# Dual_Power_Supply_Design.net
KiCad netlist of a schematic drawn in EAGLE
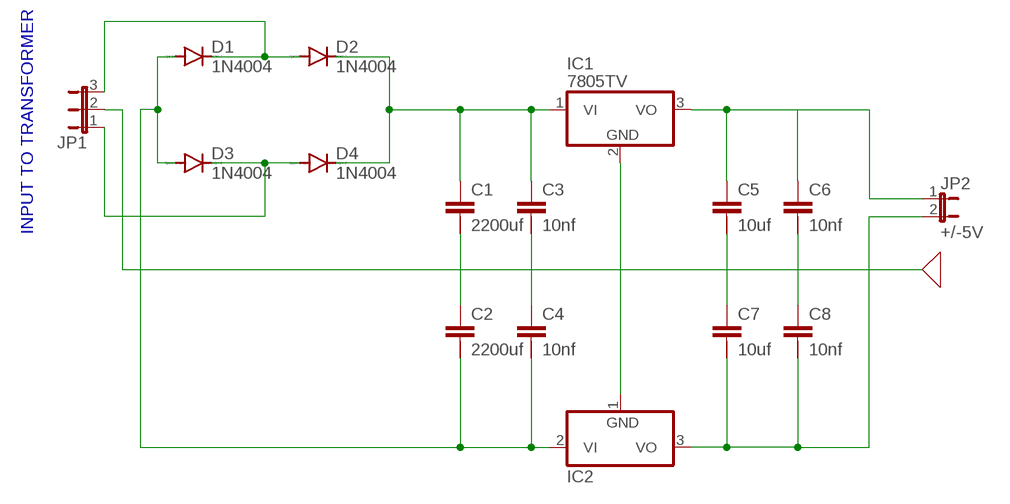
[diagram p0: schematic, sheet 1]

(export (version "E")
  (design (tool "Eeschema 10.0.6"))
  (components
    (comp (ref "C1")
      (value "2200uf")
      (footprint "eagle-import:C2.5_5-2")
      (libsource (lib "eagle-import") (part "C-2.5-5/2"))
    )
    (comp (ref "C2")
      (value "2200uf")
      (footprint "eagle-import:C2.5_5-2")
      (libsource (lib "eagle-import") (part "C-2.5-5/2"))
    )
    (comp (ref "C3")
      (value "10nf")
      (footprint "eagle-import:C2.5_5-2")
      (libsource (lib "eagle-import") (part "C-2.5-5/2"))
    )
    (comp (ref "C4")
      (value "10nf")
      (footprint "eagle-import:C2.5_5-2")
      (libsource (lib "eagle-import") (part "C-2.5-5/2"))
    )
    (comp (ref "C5")
      (value "10uf")
      (footprint "eagle-import:C2.5_5-2")
      (libsource (lib "eagle-import") (part "C-2.5-5/2"))
    )
    (comp (ref "C6")
      (value "10nf")
      (footprint "eagle-import:C2.5_5-2")
      (libsource (lib "eagle-import") (part "C-2.5-5/2"))
    )
    (comp (ref "C7")
      (value "10uf")
      (footprint "eagle-import:C2.5_5-2")
      (libsource (lib "eagle-import") (part "C-2.5-5/2"))
    )
    (comp (ref "C8")
      (value "10nf")
      (footprint "eagle-import:C2.5_5-2")
      (libsource (lib "eagle-import") (part "C-2.5-5/2"))
    )
    (comp (ref "D1")
      (value "1N4004")
      (footprint "eagle-import:DO41-10")
      (libsource (lib "eagle-import") (part "1N4004"))
    )
    (comp (ref "D2")
      (value "1N4004")
      (footprint "eagle-import:DO41-10")
      (libsource (lib "eagle-import") (part "1N4004"))
    )
    (comp (ref "D3")
      (value "1N4004")
      (footprint "eagle-import:DO41-10")
      (libsource (lib "eagle-import") (part "1N4004"))
    )
    (comp (ref "D4")
      (value "1N4004")
      (footprint "eagle-import:DO41-10")
      (libsource (lib "eagle-import") (part "1N4004"))
    )
    (comp (ref "IC1")
      (value "7805TV")
      (footprint "eagle-import:TO220V")
      (libsource (lib "eagle-import") (part "78TV05"))
    )
    (comp (ref "IC2")
      (value "7905T")
      (footprint "eagle-import:TO220H")
      (libsource (lib "eagle-import") (part "79T05"))
    )
    (comp (ref "JP1")
      (value "JP2W")
      (footprint "eagle-import:JP2W")
      (libsource (lib "eagle-import") (part "JP2W"))
    )
    (comp (ref "JP2")
      (value "+/-5V")
      (footprint "eagle-import:JP1")
      (libsource (lib "eagle-import") (part "JP1E"))
    )
  )
  (nets
    (net (code "2") (name "Net-(C1-Pad2)") (class "Default")
      (node (ref "C1") (pin "2") (pinfunction "2_2") (pintype "passive"))
      (node (ref "C2") (pin "1") (pinfunction "1_1") (pintype "passive"))
    )
    (net (code "3") (name "Net-(C3-Pad2)") (class "Default")
      (node (ref "C3") (pin "2") (pinfunction "2_2") (pintype "passive"))
      (node (ref "C4") (pin "1") (pinfunction "1_1") (pintype "passive"))
    )
    (net (code "4") (name "Net-(C5-Pad2)") (class "Default")
      (node (ref "C5") (pin "2") (pinfunction "2_2") (pintype "passive"))
      (node (ref "C7") (pin "1") (pinfunction "1_1") (pintype "passive"))
    )
    (net (code "5") (name "Net-(C6-Pad2)") (class "Default")
      (node (ref "C6") (pin "2") (pinfunction "2_2") (pintype "passive"))
      (node (ref "C8") (pin "1") (pinfunction "1_1") (pintype "passive"))
    )
    (net (code "6") (name "Net-(D1-PadC)") (class "Default")
      (node (ref "D1") (pin "C") (pinfunction "C_C") (pintype "passive"))
      (node (ref "D2") (pin "A") (pinfunction "A_A") (pintype "passive"))
      (node (ref "JP1") (pin "3") (pinfunction "3_3") (pintype "passive"))
    )
    (net (code "7") (name "Net-(D3-PadC)") (class "Default")
      (node (ref "D3") (pin "C") (pinfunction "C_C") (pintype "passive"))
      (node (ref "D4") (pin "A") (pinfunction "A_A") (pintype "passive"))
      (node (ref "JP1") (pin "1") (pinfunction "1_1") (pintype "passive"))
    )
    (net (code "8") (name "Net-(IC1-GND)") (class "Default")
      (node (ref "IC1") (pin "2") (pinfunction "GND_2") (pintype "passive"))
      (node (ref "IC2") (pin "1") (pinfunction "GND_1") (pintype "passive"))
    )
    (net (code "9") (name "Net-(IC1-VI)") (class "Default")
      (node (ref "C1") (pin "1") (pinfunction "1_1") (pintype "passive"))
      (node (ref "C3") (pin "1") (pinfunction "1_1") (pintype "passive"))
      (node (ref "D2") (pin "C") (pinfunction "C_C") (pintype "passive"))
      (node (ref "D4") (pin "C") (pinfunction "C_C") (pintype "passive"))
      (node (ref "IC1") (pin "1") (pinfunction "VI_1") (pintype "input"))
    )
    (net (code "10") (name "Net-(IC1-VO)") (class "Default")
      (node (ref "C5") (pin "1") (pinfunction "1_1") (pintype "passive"))
      (node (ref "IC1") (pin "3") (pinfunction "VO_3") (pintype "passive"))
      (node (ref "JP2") (pin "1") (pinfunction "1_1") (pintype "passive"))
    )
    (net (code "11") (name "Net-(IC2-VI)") (class "Default")
      (node (ref "C2") (pin "2") (pinfunction "2_2") (pintype "passive"))
      (node (ref "C4") (pin "2") (pinfunction "2_2") (pintype "passive"))
      (node (ref "D1") (pin "A") (pinfunction "A_A") (pintype "passive"))
      (node (ref "D3") (pin "A") (pinfunction "A_A") (pintype "passive"))
      (node (ref "IC2") (pin "2") (pinfunction "VI_2") (pintype "input"))
    )
    (net (code "12") (name "Net-(IC2-VO)") (class "Default")
      (node (ref "C7") (pin "2") (pinfunction "2_2") (pintype "passive"))
      (node (ref "C8") (pin "2") (pinfunction "2_2") (pintype "passive"))
      (node (ref "IC2") (pin "3") (pinfunction "VO_3") (pintype "passive"))
      (node (ref "JP2") (pin "2") (pinfunction "2_2") (pintype "passive"))
    )
    (net (code "13") (name "unconnected-(C1-Pad3)") (class "Default")
      (node (ref "C1") (pin "3") (pinfunction "3_3") (pintype "passive"))
    )
    (net (code "14") (name "unconnected-(C2-Pad3)") (class "Default")
      (node (ref "C2") (pin "3") (pinfunction "3_3") (pintype "passive"))
    )
    (net (code "15") (name "unconnected-(C3-Pad3)") (class "Default")
      (node (ref "C3") (pin "3") (pinfunction "3_3") (pintype "passive"))
    )
    (net (code "16") (name "unconnected-(C4-Pad3)") (class "Default")
      (node (ref "C4") (pin "3") (pinfunction "3_3") (pintype "passive"))
    )
    (net (code "17") (name "unconnected-(C5-Pad3)") (class "Default")
      (node (ref "C5") (pin "3") (pinfunction "3_3") (pintype "passive"))
    )
    (net (code "18") (name "unconnected-(C6-Pad1)") (class "Default")
      (node (ref "C6") (pin "1") (pinfunction "1_1") (pintype "passive"))
    )
    (net (code "19") (name "unconnected-(C6-Pad3)") (class "Default")
      (node (ref "C6") (pin "3") (pinfunction "3_3") (pintype "passive"))
    )
    (net (code "20") (name "unconnected-(C7-Pad3)") (class "Default")
      (node (ref "C7") (pin "3") (pinfunction "3_3") (pintype "passive"))
    )
    (net (code "21") (name "unconnected-(C8-Pad3)") (class "Default")
      (node (ref "C8") (pin "3") (pinfunction "3_3") (pintype "passive"))
    )
    (net (code "22") (name "unconnected-(JP1-Pad2)") (class "Default")
      (node (ref "JP1") (pin "2") (pinfunction "2_2") (pintype "passive"))
    )
  )
)
